# V2_1.net
KiCad netlist of a schematic drawn in EAGLE
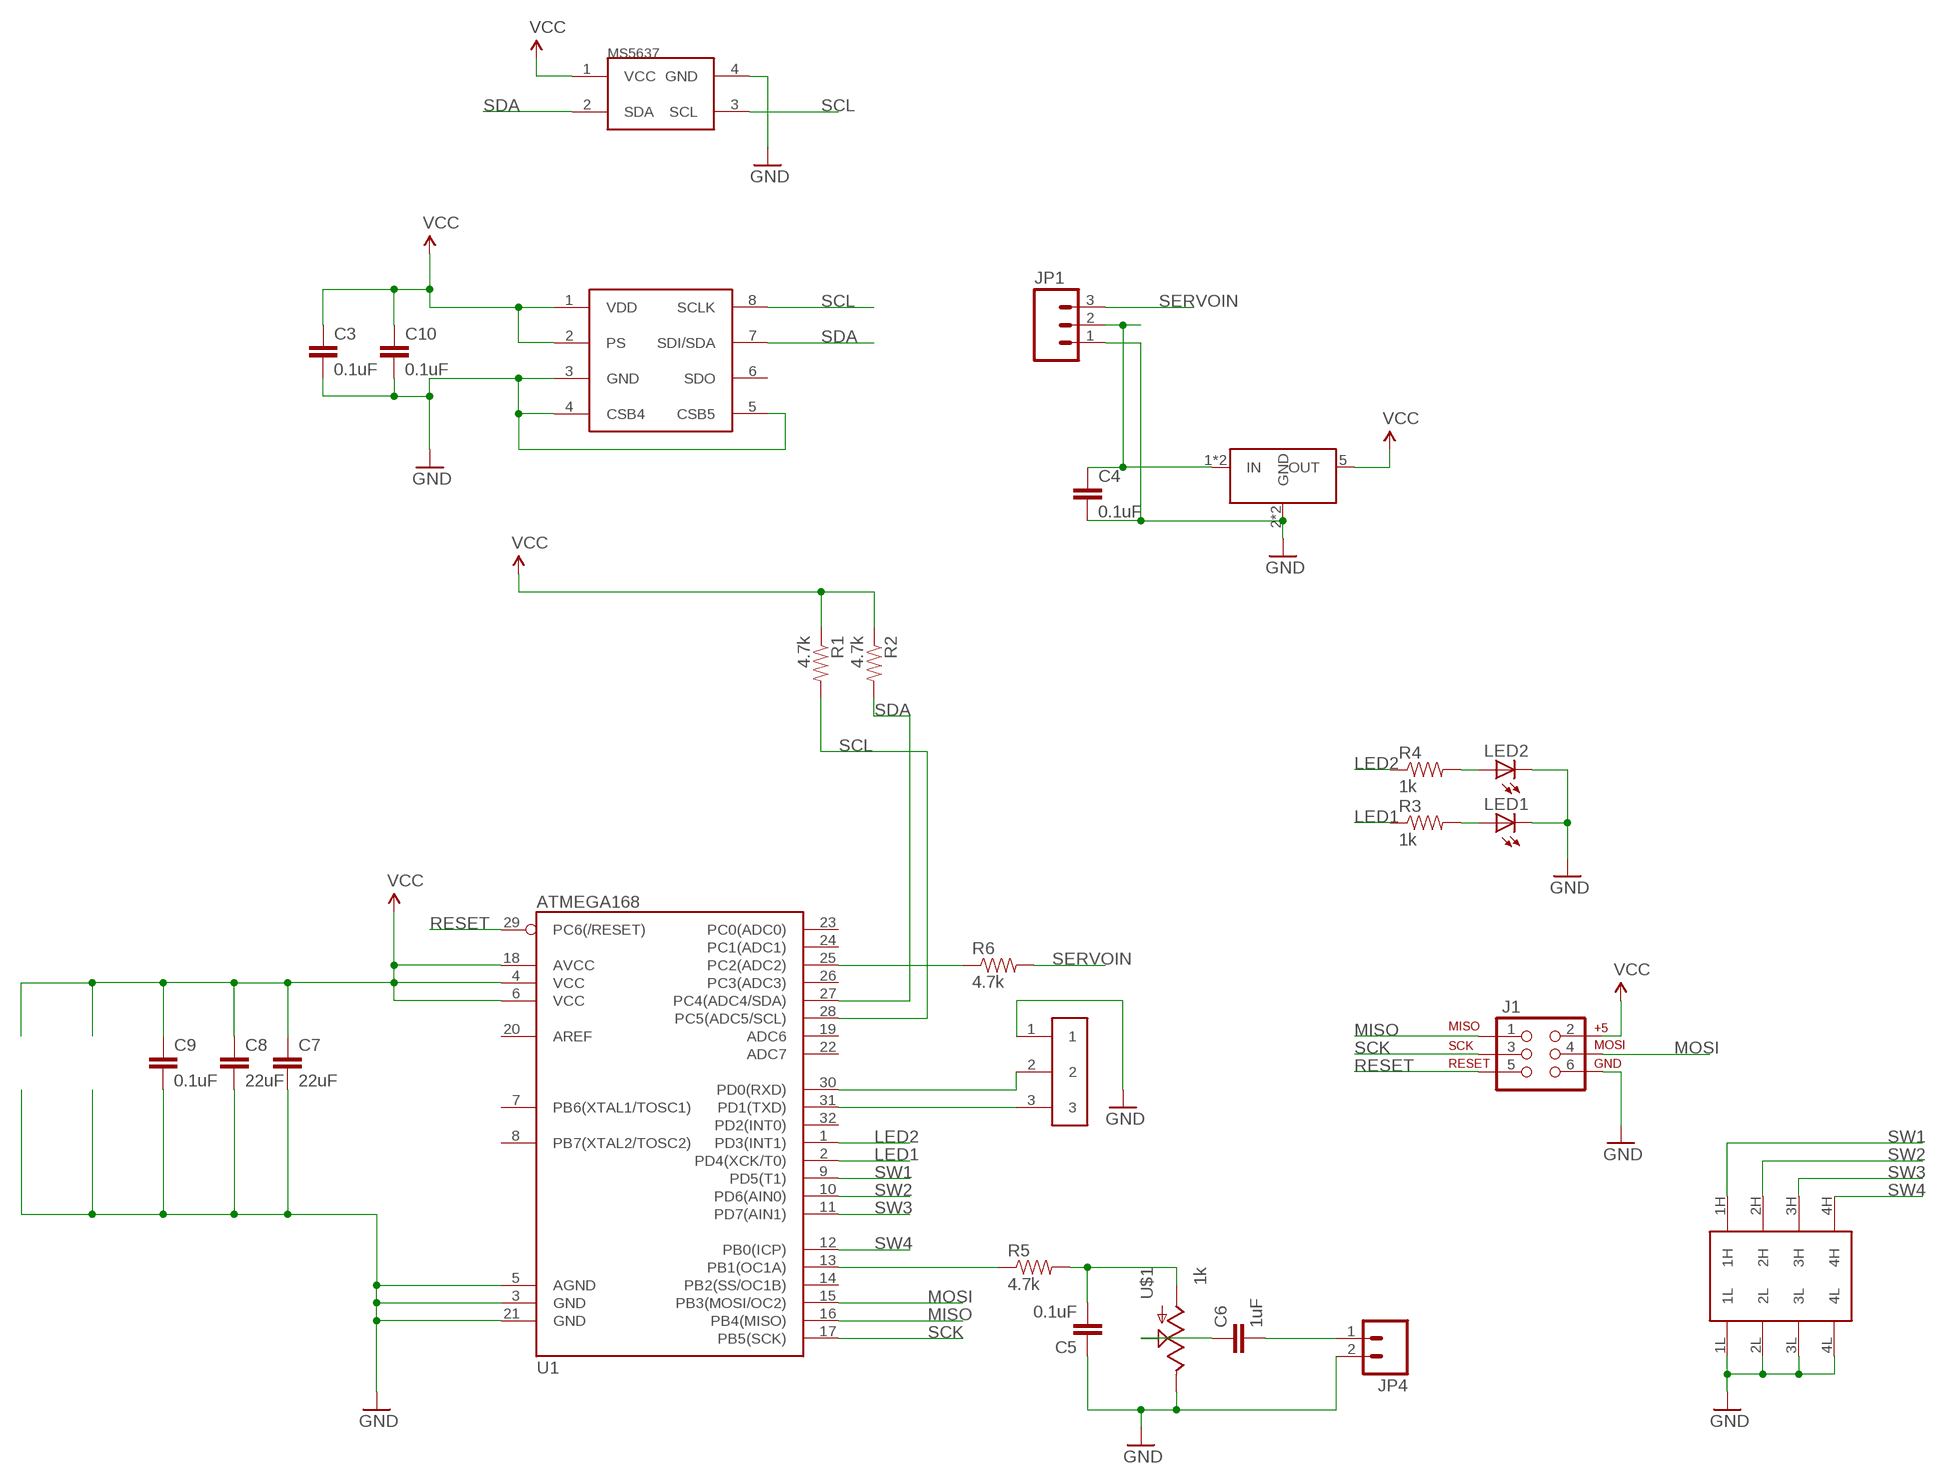
[diagram p0: schematic, sheet 1]

(export (version "E")
  (design (tool "Eeschema 10.0.6"))
  (components
    (comp (ref "C3")
      (value "0.1uF")
      (footprint "eagle-import:0603-CAP")
      (libsource (lib "eagle-import") (part "CAP0603-CAP"))
    )
    (comp (ref "C4")
      (value "0.1uF")
      (footprint "eagle-import:0603-CAP")
      (libsource (lib "eagle-import") (part "CAP0603-CAP"))
    )
    (comp (ref "C5")
      (value "0.1uF")
      (footprint "eagle-import:0603-CAP")
      (libsource (lib "eagle-import") (part "CAP0603-CAP"))
    )
    (comp (ref "C6")
      (value "1uF")
      (footprint "eagle-import:0603-CAP")
      (libsource (lib "eagle-import") (part "CAP0603-CAP"))
    )
    (comp (ref "C7")
      (value "22uF")
      (footprint "eagle-import:0805")
      (libsource (lib "eagle-import") (part "CAP0805"))
    )
    (comp (ref "C8")
      (value "22uF")
      (footprint "eagle-import:0805")
      (libsource (lib "eagle-import") (part "CAP0805"))
    )
    (comp (ref "C9")
      (value "0.1uF")
      (footprint "eagle-import:0603-CAP")
      (libsource (lib "eagle-import") (part "CAP0603-CAP"))
    )
    (comp (ref "C10")
      (value "0.1uF")
      (footprint "eagle-import:0603-CAP")
      (libsource (lib "eagle-import") (part "CAP0603-CAP"))
    )
    (comp (ref "J1")
      (value "AVR_SPI_PRG_6NS")
      (footprint "eagle-import:2X3-NS")
      (libsource (lib "eagle-import") (part "AVR_SPI_PRG_6NS"))
    )
    (comp (ref "JP1")
      (value "M03PTH")
      (footprint "eagle-import:1X03")
      (libsource (lib "eagle-import") (part "M03PTH"))
    )
    (comp (ref "JP4")
      (value "M02PTH")
      (footprint "eagle-import:1X02")
      (libsource (lib "eagle-import") (part "M02PTH"))
    )
    (comp (ref "LED1")
      (value "LED0603")
      (footprint "eagle-import:LED-0603")
      (libsource (lib "eagle-import") (part "LED0603"))
    )
    (comp (ref "LED2")
      (value "LED0603")
      (footprint "eagle-import:LED-0603")
      (libsource (lib "eagle-import") (part "LED0603"))
    )
    (comp (ref "R1")
      (value "4.7k")
      (footprint "eagle-import:0603-RES")
      (libsource (lib "eagle-import") (part "RESISTOR0603-RES"))
    )
    (comp (ref "R2")
      (value "4.7k")
      (footprint "eagle-import:0603-RES")
      (libsource (lib "eagle-import") (part "RESISTOR0603-RES"))
    )
    (comp (ref "R3")
      (value "1k")
      (footprint "eagle-import:0603-RES")
      (libsource (lib "eagle-import") (part "RESISTOR0603-RES"))
    )
    (comp (ref "R4")
      (value "1k")
      (footprint "eagle-import:0603-RES")
      (libsource (lib "eagle-import") (part "RESISTOR0603-RES"))
    )
    (comp (ref "R5")
      (value "4.7k")
      (footprint "eagle-import:0603-RES")
      (libsource (lib "eagle-import") (part "RESISTOR0603-RES"))
    )
    (comp (ref "R6")
      (value "4.7k")
      (footprint "eagle-import:0603-RES")
      (libsource (lib "eagle-import") (part "RESISTOR0603-RES"))
    )
    (comp (ref "U$1")
      (value "1k")
      (footprint "eagle-import:BOURNS_3306KPW")
      (libsource (lib "eagle-import") (part "POTBOURNS_3306KPW"))
    )
    (comp (ref "U$2")
      (value "MS5611")
      (footprint "eagle-import:MS5611")
      (libsource (lib "eagle-import") (part "MS5611"))
    )
    (comp (ref "U$3")
      (value "LINEAR_REGSOT23-5_TOREX")
      (footprint "eagle-import:SOT23-5")
      (libsource (lib "eagle-import") (part "LINEAR_REGSOT23-5_TOREX"))
    )
    (comp (ref "U$4")
      (value "MS5637")
      (footprint "eagle-import:MS5637")
      (libsource (lib "eagle-import") (part "MS5637"))
    )
    (comp (ref "U$5")
      (value "DIP_SWITCH")
      (footprint "eagle-import:DIPSWITCH4")
      (libsource (lib "eagle-import") (part "DIP_SWITCH"))
    )
    (comp (ref "U$6")
      (value "HEADER3")
      (footprint "eagle-import:PAD3_1X1")
      (libsource (lib "eagle-import") (part "HEADER3"))
    )
    (comp (ref "U1")
      (value "ATMEGA168")
      (footprint "eagle-import:TQFP32-08")
      (libsource (lib "eagle-import") (part "ATMEGA168"))
    )
  )
  (nets
    (net (code "1") (name "/LED1") (class "Default")
      (node (ref "R3") (pin "1") (pinfunction "1_1") (pintype "passive"))
      (node (ref "U1") (pin "2") (pinfunction "PD4(XCK/T0)_2") (pintype "bidirectional"))
    )
    (net (code "2") (name "/LED2") (class "Default")
      (node (ref "R4") (pin "1") (pinfunction "1_1") (pintype "passive"))
      (node (ref "U1") (pin "1") (pinfunction "PD3(INT1)_1") (pintype "bidirectional"))
    )
    (net (code "3") (name "/MISO") (class "Default")
      (node (ref "J1") (pin "1") (pinfunction "1_1") (pintype "passive"))
      (node (ref "U1") (pin "16") (pinfunction "PB4(MISO)_16") (pintype "bidirectional"))
    )
    (net (code "4") (name "/MOSI") (class "Default")
      (node (ref "J1") (pin "4") (pinfunction "4_4") (pintype "passive"))
      (node (ref "U1") (pin "15") (pinfunction "PB3(MOSI/OC2)_15") (pintype "bidirectional"))
    )
    (net (code "5") (name "/RESET") (class "Default")
      (node (ref "J1") (pin "5") (pinfunction "5_5") (pintype "passive"))
      (node (ref "U1") (pin "29") (pinfunction "PC6(/RESET)_29") (pintype "bidirectional"))
    )
    (net (code "6") (name "/SCK") (class "Default")
      (node (ref "J1") (pin "3") (pinfunction "3_3") (pintype "passive"))
      (node (ref "U1") (pin "17") (pinfunction "PB5(SCK)_17") (pintype "bidirectional"))
    )
    (net (code "7") (name "/SCL") (class "Default")
      (node (ref "R1") (pin "2") (pinfunction "2_2") (pintype "passive"))
      (node (ref "U$2") (pin "8") (pinfunction "SCLK_8") (pintype "bidirectional"))
      (node (ref "U$4") (pin "3") (pinfunction "SCL_3") (pintype "bidirectional"))
      (node (ref "U1") (pin "28") (pinfunction "PC5(ADC5/SCL)_28") (pintype "bidirectional"))
    )
    (net (code "8") (name "/SDA") (class "Default")
      (node (ref "R2") (pin "2") (pinfunction "2_2") (pintype "passive"))
      (node (ref "U$2") (pin "7") (pinfunction "SDI/SDA_7") (pintype "bidirectional"))
      (node (ref "U$4") (pin "2") (pinfunction "SDA_2") (pintype "bidirectional"))
      (node (ref "U1") (pin "27") (pinfunction "PC4(ADC4/SDA)_27") (pintype "bidirectional"))
    )
    (net (code "9") (name "/SERVOIN") (class "Default")
      (node (ref "JP1") (pin "3") (pinfunction "3_3") (pintype "passive"))
      (node (ref "R6") (pin "2") (pinfunction "2_2") (pintype "passive"))
    )
    (net (code "10") (name "/SW1") (class "Default")
      (node (ref "U$5") (pin "1H") (pinfunction "1H_1H") (pintype "bidirectional"))
      (node (ref "U1") (pin "9") (pinfunction "PD5(T1)_9") (pintype "bidirectional"))
    )
    (net (code "11") (name "/SW2") (class "Default")
      (node (ref "U$5") (pin "2H") (pinfunction "2H_2H") (pintype "bidirectional"))
      (node (ref "U1") (pin "10") (pinfunction "PD6(AIN0)_10") (pintype "bidirectional"))
    )
    (net (code "12") (name "/SW3") (class "Default")
      (node (ref "U$5") (pin "3H") (pinfunction "3H_3H") (pintype "bidirectional"))
      (node (ref "U1") (pin "11") (pinfunction "PD7(AIN1)_11") (pintype "bidirectional"))
    )
    (net (code "13") (name "/SW4") (class "Default")
      (node (ref "U$5") (pin "4H") (pinfunction "4H_4H") (pintype "bidirectional"))
      (node (ref "U1") (pin "12") (pinfunction "PB0(ICP)_12") (pintype "bidirectional"))
    )
    (net (code "14") (name "GND") (class "Default")
      (node (ref "C10") (pin "2") (pinfunction "2_2") (pintype "passive"))
      (node (ref "C3") (pin "2") (pinfunction "2_2") (pintype "passive"))
      (node (ref "C4") (pin "2") (pinfunction "2_2") (pintype "passive"))
      (node (ref "C5") (pin "1") (pinfunction "1_1") (pintype "passive"))
      (node (ref "C7") (pin "2") (pinfunction "2_2") (pintype "passive"))
      (node (ref "C8") (pin "2") (pinfunction "2_2") (pintype "passive"))
      (node (ref "C9") (pin "2") (pinfunction "2_2") (pintype "passive"))
      (node (ref "J1") (pin "6") (pinfunction "6_6") (pintype "passive"))
      (node (ref "JP1") (pin "1") (pinfunction "1_1") (pintype "passive"))
      (node (ref "JP4") (pin "2") (pinfunction "2_2") (pintype "passive"))
      (node (ref "LED1") (pin "C") (pinfunction "C_C") (pintype "passive"))
      (node (ref "LED2") (pin "C") (pinfunction "C_C") (pintype "passive"))
      (node (ref "U$1") (pin "1") (pinfunction "E_1") (pintype "passive"))
      (node (ref "U$2") (pin "3") (pinfunction "GND_3") (pintype "bidirectional"))
      (node (ref "U$2") (pin "4") (pinfunction "CSB4_4") (pintype "bidirectional"))
      (node (ref "U$2") (pin "5") (pinfunction "CSB5_5") (pintype "bidirectional"))
      (node (ref "U$3") (pin "2") (pinfunction "GND_2") (pintype "power_in"))
      (node (ref "U$3") (pin "3") (pinfunction "GND_3") (pintype "power_in"))
      (node (ref "U$4") (pin "4") (pinfunction "GND_4") (pintype "bidirectional"))
      (node (ref "U$5") (pin "1L") (pinfunction "1L_1L") (pintype "bidirectional"))
      (node (ref "U$5") (pin "2L") (pinfunction "2L_2L") (pintype "bidirectional"))
      (node (ref "U$5") (pin "3L") (pinfunction "3L_3L") (pintype "bidirectional"))
      (node (ref "U$5") (pin "4L") (pinfunction "4L_4L") (pintype "bidirectional"))
      (node (ref "U$6") (pin "1") (pinfunction "1_1") (pintype "bidirectional"))
      (node (ref "U1") (pin "21") (pinfunction "GND_21") (pintype "bidirectional"))
      (node (ref "U1") (pin "3") (pinfunction "GND_3") (pintype "bidirectional"))
      (node (ref "U1") (pin "5") (pinfunction "AGND_5") (pintype "bidirectional"))
    )
    (net (code "15") (name "Net-(C4-Pad1)") (class "Default")
      (node (ref "C4") (pin "1") (pinfunction "1_1") (pintype "passive"))
      (node (ref "JP1") (pin "2") (pinfunction "2_2") (pintype "passive"))
      (node (ref "U$3") (pin "1") (pinfunction "IN_1") (pintype "power_in"))
      (node (ref "U$3") (pin "4") (pinfunction "IN_4") (pintype "power_in"))
    )
    (net (code "16") (name "Net-(C6-Pad2)") (class "Default")
      (node (ref "C6") (pin "2") (pinfunction "2_2") (pintype "passive"))
      (node (ref "JP4") (pin "1") (pinfunction "1_1") (pintype "passive"))
    )
    (net (code "17") (name "Net-(LED1-PadA)") (class "Default")
      (node (ref "LED1") (pin "A") (pinfunction "A_A") (pintype "passive"))
      (node (ref "R3") (pin "2") (pinfunction "2_2") (pintype "passive"))
    )
    (net (code "18") (name "Net-(LED2-PadA)") (class "Default")
      (node (ref "LED2") (pin "A") (pinfunction "A_A") (pintype "passive"))
      (node (ref "R4") (pin "2") (pinfunction "2_2") (pintype "passive"))
    )
    (net (code "19") (name "Net-(U$1-A)") (class "Default")
      (node (ref "C5") (pin "2") (pinfunction "2_2") (pintype "passive"))
      (node (ref "R5") (pin "2") (pinfunction "2_2") (pintype "passive"))
      (node (ref "U$1") (pin "3") (pinfunction "A_3") (pintype "passive"))
    )
    (net (code "20") (name "Net-(U$1-S)") (class "Default")
      (node (ref "C6") (pin "1") (pinfunction "1_1") (pintype "passive"))
      (node (ref "U$1") (pin "2") (pinfunction "S_2") (pintype "passive"))
    )
    (net (code "21") (name "Net-(U1-PB1(OC1A))") (class "Default")
      (node (ref "R5") (pin "1") (pinfunction "1_1") (pintype "passive"))
      (node (ref "U1") (pin "13") (pinfunction "PB1(OC1A)_13") (pintype "bidirectional"))
    )
    (net (code "22") (name "Net-(U1-PC2(ADC2))") (class "Default")
      (node (ref "R6") (pin "1") (pinfunction "1_1") (pintype "passive"))
      (node (ref "U1") (pin "25") (pinfunction "PC2(ADC2)_25") (pintype "bidirectional"))
    )
    (net (code "23") (name "Net-(U1-PD0(RXD))") (class "Default")
      (node (ref "U$6") (pin "2") (pinfunction "2_2") (pintype "bidirectional"))
      (node (ref "U1") (pin "30") (pinfunction "PD0(RXD)_30") (pintype "bidirectional"))
    )
    (net (code "24") (name "Net-(U1-PD1(TXD))") (class "Default")
      (node (ref "U$6") (pin "3") (pinfunction "3_3") (pintype "bidirectional"))
      (node (ref "U1") (pin "31") (pinfunction "PD1(TXD)_31") (pintype "bidirectional"))
    )
    (net (code "25") (name "VCC") (class "Default")
      (node (ref "C10") (pin "1") (pinfunction "1_1") (pintype "passive"))
      (node (ref "C3") (pin "1") (pinfunction "1_1") (pintype "passive"))
      (node (ref "C7") (pin "1") (pinfunction "1_1") (pintype "passive"))
      (node (ref "C8") (pin "1") (pinfunction "1_1") (pintype "passive"))
      (node (ref "C9") (pin "1") (pinfunction "1_1") (pintype "passive"))
      (node (ref "J1") (pin "2") (pinfunction "2_2") (pintype "passive"))
      (node (ref "R1") (pin "1") (pinfunction "1_1") (pintype "passive"))
      (node (ref "R2") (pin "1") (pinfunction "1_1") (pintype "passive"))
      (node (ref "U$2") (pin "1") (pinfunction "VDD_1") (pintype "bidirectional"))
      (node (ref "U$2") (pin "2") (pinfunction "PS_2") (pintype "bidirectional"))
      (node (ref "U$3") (pin "5") (pinfunction "OUT_5") (pintype "power_in"))
      (node (ref "U$4") (pin "1") (pinfunction "VCC_1") (pintype "bidirectional"))
      (node (ref "U1") (pin "18") (pinfunction "AVCC_18") (pintype "bidirectional"))
      (node (ref "U1") (pin "4") (pinfunction "VCC_4") (pintype "bidirectional"))
      (node (ref "U1") (pin "6") (pinfunction "VCC_6") (pintype "bidirectional"))
    )
    (net (code "26") (name "unconnected-(U$2-SDO-Pad6)") (class "Default")
      (node (ref "U$2") (pin "6") (pinfunction "SDO_6") (pintype "bidirectional"))
    )
    (net (code "27") (name "unconnected-(U1-ADC6-Pad19)") (class "Default")
      (node (ref "U1") (pin "19") (pinfunction "ADC6_19") (pintype "bidirectional"))
    )
    (net (code "28") (name "unconnected-(U1-ADC7-Pad22)") (class "Default")
      (node (ref "U1") (pin "22") (pinfunction "ADC7_22") (pintype "bidirectional"))
    )
    (net (code "29") (name "unconnected-(U1-AREF-Pad20)") (class "Default")
      (node (ref "U1") (pin "20") (pinfunction "AREF_20") (pintype "bidirectional"))
    )
    (net (code "30") (name "unconnected-(U1-PB2(SS{slash}OC1B)-Pad14)") (class "Default")
      (node (ref "U1") (pin "14") (pinfunction "PB2(SS/OC1B)_14") (pintype "bidirectional"))
    )
    (net (code "31") (name "unconnected-(U1-PB6(XTAL1{slash}TOSC1)-Pad7)") (class "Default")
      (node (ref "U1") (pin "7") (pinfunction "PB6(XTAL1/TOSC1)_7") (pintype "bidirectional"))
    )
    (net (code "32") (name "unconnected-(U1-PB7(XTAL2{slash}TOSC2)-Pad8)") (class "Default")
      (node (ref "U1") (pin "8") (pinfunction "PB7(XTAL2/TOSC2)_8") (pintype "bidirectional"))
    )
    (net (code "33") (name "unconnected-(U1-PC0(ADC0)-Pad23)") (class "Default")
      (node (ref "U1") (pin "23") (pinfunction "PC0(ADC0)_23") (pintype "bidirectional"))
    )
    (net (code "34") (name "unconnected-(U1-PC1(ADC1)-Pad24)") (class "Default")
      (node (ref "U1") (pin "24") (pinfunction "PC1(ADC1)_24") (pintype "bidirectional"))
    )
    (net (code "35") (name "unconnected-(U1-PC3(ADC3)-Pad26)") (class "Default")
      (node (ref "U1") (pin "26") (pinfunction "PC3(ADC3)_26") (pintype "bidirectional"))
    )
    (net (code "36") (name "unconnected-(U1-PD2(INT0)-Pad32)") (class "Default")
      (node (ref "U1") (pin "32") (pinfunction "PD2(INT0)_32") (pintype "bidirectional"))
    )
  )
)
